# EasyCheck_rev2_interface.net
KiCad netlist of a schematic drawn in EAGLE
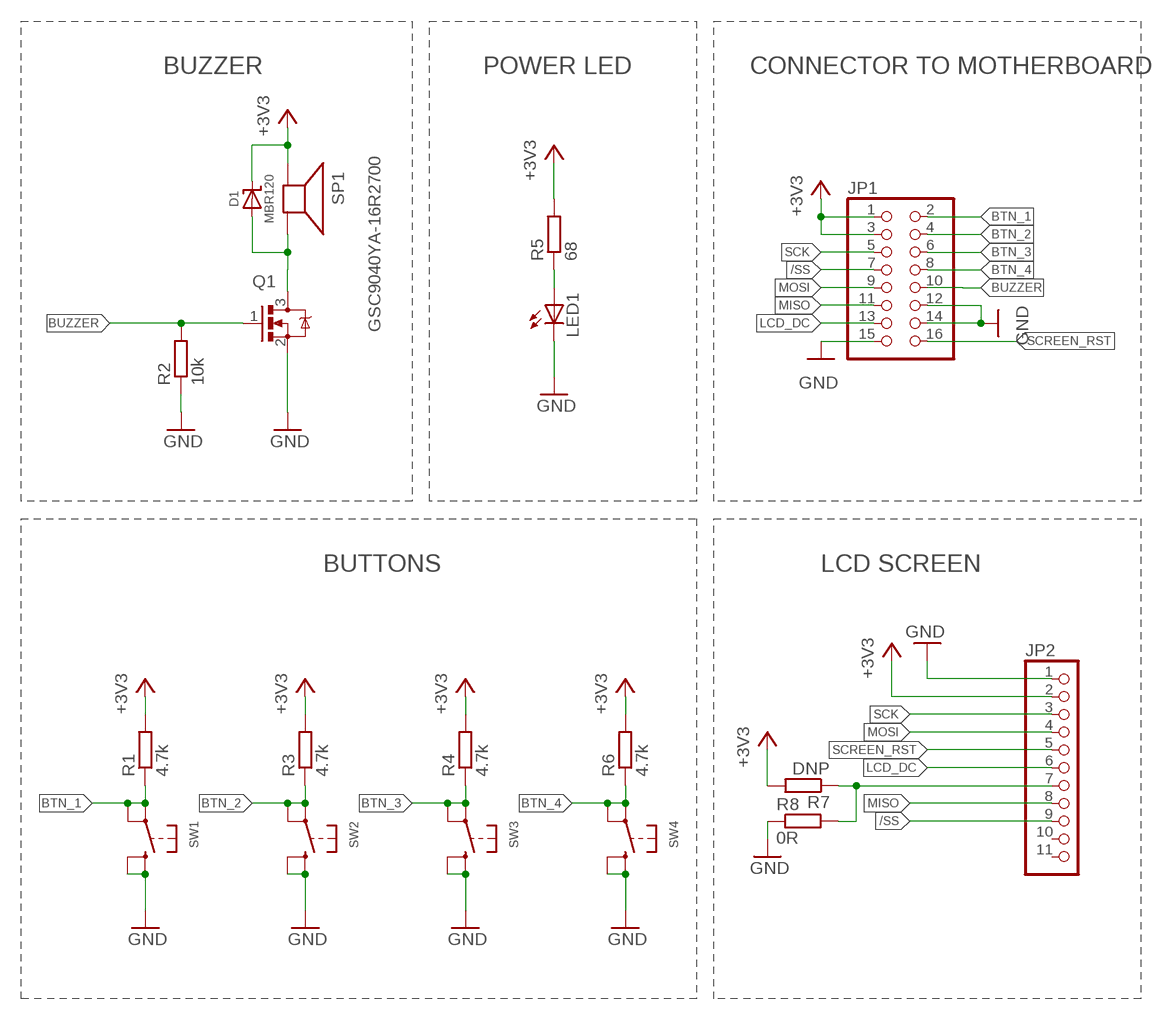
[diagram p0: schematic, sheet 1]

(export (version "E")
  (design (tool "Eeschema 10.0.6"))
  (components
    (comp (ref "D1")
      (value "MBR120")
      (footprint "eagle-import:MICROBUILDER_SOD-123")
      (libsource (lib "eagle-import") (part "MICROBUILDER_DIODE-SCHOTTKYSOD-123"))
    )
    (comp (ref "JP1")
      (value "PINHD-2X8")
      (footprint "eagle-import:2X08")
      (libsource (lib "eagle-import") (part "PINHD-2X8"))
    )
    (comp (ref "JP2")
      (value "PINHD-1X11")
      (footprint "eagle-import:1X11")
      (libsource (lib "eagle-import") (part "PINHD-1X11"))
    )
    (comp (ref "LED1")
      (value "LEDCHIPLED_0603")
      (footprint "eagle-import:CHIPLED_0603")
      (libsource (lib "eagle-import") (part "LEDCHIPLED_0603"))
    )
    (comp (ref "Q1")
      (value "DMN6140L")
      (footprint "eagle-import:SOT91P240X110-3N")
      (libsource (lib "eagle-import") (part "DMN6140L"))
    )
    (comp (ref "R1")
      (value "4.7k")
      (footprint "eagle-import:R0603")
      (libsource (lib "eagle-import") (part "R-EU_R0603"))
    )
    (comp (ref "R2")
      (value "10k")
      (footprint "eagle-import:R0603")
      (libsource (lib "eagle-import") (part "R-EU_R0603"))
    )
    (comp (ref "R3")
      (value "4.7k")
      (footprint "eagle-import:R0603")
      (libsource (lib "eagle-import") (part "R-EU_R0603"))
    )
    (comp (ref "R4")
      (value "4.7k")
      (footprint "eagle-import:R0603")
      (libsource (lib "eagle-import") (part "R-EU_R0603"))
    )
    (comp (ref "R5")
      (value "68")
      (footprint "eagle-import:R0603")
      (libsource (lib "eagle-import") (part "R-EU_R0603"))
    )
    (comp (ref "R6")
      (value "4.7k")
      (footprint "eagle-import:R0603")
      (libsource (lib "eagle-import") (part "R-EU_R0603"))
    )
    (comp (ref "R7")
      (value "DNP")
      (footprint "eagle-import:R0603")
      (libsource (lib "eagle-import") (part "R-EU_R0603"))
    )
    (comp (ref "R8")
      (value "0R")
      (footprint "eagle-import:R0603")
      (libsource (lib "eagle-import") (part "R-EU_R0603"))
    )
    (comp (ref "SP1")
      (value "GSC9040YA-16R2700")
      (footprint "eagle-import:GSC9040YA-16R2700")
      (libsource (lib "eagle-import") (part "GSC9040YA-16R2700"))
    )
    (comp (ref "SW1")
      (value "MICROBUILDER_SWITCH_TACT_SMT_EVQQ2_SMALL")
      (footprint "eagle-import:MICROBUILDER_EVQ-Q2_SMALLER")
      (libsource (lib "eagle-import") (part "MICROBUILDER_SWITCH_TACT_SMT_EVQQ2_SMALL"))
    )
    (comp (ref "SW2")
      (value "MICROBUILDER_SWITCH_TACT_SMT_EVQQ2_SMALL")
      (footprint "eagle-import:MICROBUILDER_EVQ-Q2_SMALLER")
      (libsource (lib "eagle-import") (part "MICROBUILDER_SWITCH_TACT_SMT_EVQQ2_SMALL"))
    )
    (comp (ref "SW3")
      (value "MICROBUILDER_SWITCH_TACT_SMT_EVQQ2_SMALL")
      (footprint "eagle-import:MICROBUILDER_EVQ-Q2_SMALLER")
      (libsource (lib "eagle-import") (part "MICROBUILDER_SWITCH_TACT_SMT_EVQQ2_SMALL"))
    )
    (comp (ref "SW4")
      (value "MICROBUILDER_SWITCH_TACT_SMT_EVQQ2_SMALL")
      (footprint "eagle-import:MICROBUILDER_EVQ-Q2_SMALLER")
      (libsource (lib "eagle-import") (part "MICROBUILDER_SWITCH_TACT_SMT_EVQQ2_SMALL"))
    )
  )
  (nets
    (net (code "1") (name "+3V3") (class "Default")
      (node (ref "D1") (pin "C") (pinfunction "C_C") (pintype "passive"))
      (node (ref "JP1") (pin "1") (pinfunction "1_1") (pintype "passive"))
      (node (ref "JP1") (pin "3") (pinfunction "3_3") (pintype "passive"))
      (node (ref "JP2") (pin "2") (pinfunction "2_2") (pintype "passive"))
      (node (ref "R1") (pin "2") (pinfunction "2_2") (pintype "passive"))
      (node (ref "R3") (pin "2") (pinfunction "2_2") (pintype "passive"))
      (node (ref "R4") (pin "2") (pinfunction "2_2") (pintype "passive"))
      (node (ref "R5") (pin "2") (pinfunction "2_2") (pintype "passive"))
      (node (ref "R6") (pin "2") (pinfunction "2_2") (pintype "passive"))
      (node (ref "R7") (pin "2") (pinfunction "2_2") (pintype "passive"))
      (node (ref "SP1") (pin "P$3") (pinfunction "+_P$3") (pintype "passive"))
    )
    (net (code "2") (name "BTN_1") (class "Default")
      (node (ref "JP1") (pin "2") (pinfunction "2_2") (pintype "passive"))
      (node (ref "R1") (pin "1") (pinfunction "1_1") (pintype "passive"))
      (node (ref "SW1") (pin "A") (pinfunction "P_A") (pintype "passive"))
      (node (ref "SW1") (pin "A'") (pinfunction "P1_A'") (pintype "passive"))
    )
    (net (code "3") (name "BTN_2") (class "Default")
      (node (ref "JP1") (pin "4") (pinfunction "4_4") (pintype "passive"))
      (node (ref "R3") (pin "1") (pinfunction "1_1") (pintype "passive"))
      (node (ref "SW2") (pin "A") (pinfunction "P_A") (pintype "passive"))
      (node (ref "SW2") (pin "A'") (pinfunction "P1_A'") (pintype "passive"))
    )
    (net (code "4") (name "BTN_3") (class "Default")
      (node (ref "JP1") (pin "6") (pinfunction "6_6") (pintype "passive"))
      (node (ref "R4") (pin "1") (pinfunction "1_1") (pintype "passive"))
      (node (ref "SW3") (pin "A") (pinfunction "P_A") (pintype "passive"))
      (node (ref "SW3") (pin "A'") (pinfunction "P1_A'") (pintype "passive"))
    )
    (net (code "5") (name "BTN_4") (class "Default")
      (node (ref "JP1") (pin "8") (pinfunction "8_8") (pintype "passive"))
      (node (ref "R6") (pin "1") (pinfunction "1_1") (pintype "passive"))
      (node (ref "SW4") (pin "A") (pinfunction "P_A") (pintype "passive"))
      (node (ref "SW4") (pin "A'") (pinfunction "P1_A'") (pintype "passive"))
    )
    (net (code "6") (name "BUZZER") (class "Default")
      (node (ref "JP1") (pin "10") (pinfunction "10_10") (pintype "passive"))
      (node (ref "Q1") (pin "1") (pinfunction "1_1") (pintype "bidirectional"))
      (node (ref "R2") (pin "2") (pinfunction "2_2") (pintype "passive"))
    )
    (net (code "7") (name "GND") (class "Default")
      (node (ref "JP1") (pin "12") (pinfunction "12_12") (pintype "passive"))
      (node (ref "JP1") (pin "14") (pinfunction "14_14") (pintype "passive"))
      (node (ref "JP1") (pin "15") (pinfunction "15_15") (pintype "passive"))
      (node (ref "JP2") (pin "1") (pinfunction "1_1") (pintype "passive"))
      (node (ref "LED1") (pin "C") (pinfunction "C_C") (pintype "passive"))
      (node (ref "Q1") (pin "2") (pinfunction "2_2") (pintype "bidirectional"))
      (node (ref "R2") (pin "1") (pinfunction "1_1") (pintype "passive"))
      (node (ref "R8") (pin "1") (pinfunction "1_1") (pintype "passive"))
      (node (ref "SW1") (pin "B") (pinfunction "S_B") (pintype "passive"))
      (node (ref "SW1") (pin "B'") (pinfunction "S1_B'") (pintype "passive"))
      (node (ref "SW2") (pin "B") (pinfunction "S_B") (pintype "passive"))
      (node (ref "SW2") (pin "B'") (pinfunction "S1_B'") (pintype "passive"))
      (node (ref "SW3") (pin "B") (pinfunction "S_B") (pintype "passive"))
      (node (ref "SW3") (pin "B'") (pinfunction "S1_B'") (pintype "passive"))
      (node (ref "SW4") (pin "B") (pinfunction "S_B") (pintype "passive"))
      (node (ref "SW4") (pin "B'") (pinfunction "S1_B'") (pintype "passive"))
    )
    (net (code "8") (name "LCD_DC") (class "Default")
      (node (ref "JP1") (pin "13") (pinfunction "13_13") (pintype "passive"))
      (node (ref "JP2") (pin "6") (pinfunction "6_6") (pintype "passive"))
    )
    (net (code "9") (name "MISO") (class "Default")
      (node (ref "JP1") (pin "11") (pinfunction "11_11") (pintype "passive"))
      (node (ref "JP2") (pin "8") (pinfunction "8_8") (pintype "passive"))
    )
    (net (code "10") (name "MOSI") (class "Default")
      (node (ref "JP1") (pin "9") (pinfunction "9_9") (pintype "passive"))
      (node (ref "JP2") (pin "4") (pinfunction "4_4") (pintype "passive"))
    )
    (net (code "11") (name "Net-(JP2-Pad7)") (class "Default")
      (node (ref "JP2") (pin "7") (pinfunction "7_7") (pintype "passive"))
      (node (ref "R7") (pin "1") (pinfunction "1_1") (pintype "passive"))
      (node (ref "R8") (pin "2") (pinfunction "2_2") (pintype "passive"))
    )
    (net (code "12") (name "Net-(LED1-PadA)") (class "Default")
      (node (ref "LED1") (pin "A") (pinfunction "A_A") (pintype "passive"))
      (node (ref "R5") (pin "1") (pinfunction "1_1") (pintype "passive"))
    )
    (net (code "13") (name "Net-(SP1--)") (class "Default")
      (node (ref "D1") (pin "A") (pinfunction "A_A") (pintype "passive"))
      (node (ref "Q1") (pin "3") (pinfunction "3_3") (pintype "bidirectional"))
      (node (ref "SP1") (pin "P$2") (pinfunction "-_P$2") (pintype "passive"))
    )
    (net (code "14") (name "SCK") (class "Default")
      (node (ref "JP1") (pin "5") (pinfunction "5_5") (pintype "passive"))
      (node (ref "JP2") (pin "3") (pinfunction "3_3") (pintype "passive"))
    )
    (net (code "15") (name "SCREEN_RST") (class "Default")
      (node (ref "JP1") (pin "16") (pinfunction "16_16") (pintype "passive"))
      (node (ref "JP2") (pin "5") (pinfunction "5_5") (pintype "passive"))
    )
    (net (code "16") (name "unconnected-(JP2-Pad10)") (class "Default")
      (node (ref "JP2") (pin "10") (pinfunction "10_10") (pintype "passive"))
    )
    (net (code "17") (name "unconnected-(JP2-Pad11)") (class "Default")
      (node (ref "JP2") (pin "11") (pinfunction "11_11") (pintype "passive"))
    )
    (net (code "18") (name "{slash}SS") (class "Default")
      (node (ref "JP1") (pin "7") (pinfunction "7_7") (pintype "passive"))
      (node (ref "JP2") (pin "9") (pinfunction "9_9") (pintype "passive"))
    )
  )
)
